# HighCurrentSwitches.net
KiCad netlist of a schematic drawn in Altium Designer
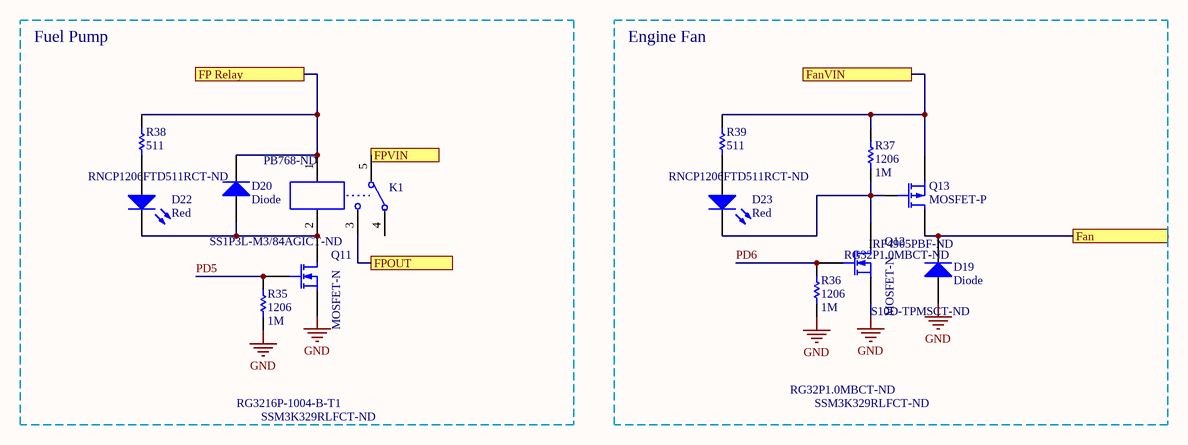
[diagram p0: HighCurrentSwitches.SchDoc]

(export (version "E")
  (design (tool "Eeschema 10.0.6"))
  (components
    (comp (ref "D19")
      (value "Diode")
      (footprint "SMC")
      (description "Default Diode")
      (fields
        (field (name "SUPPLIER PART NUMBER") "S10D-TPMSCT-ND")
        (field (name "PUBLISHER") "Altium Limited")
      )
      (libsource (lib "Miscellaneous Devices") (part "Diode"))
    )
    (comp (ref "D20")
      (value "Diode")
      (footprint "DO-220AA")
      (description "Switching diode")
      (fields
        (field (name "SUPPLIER PART NUMBER") "SS1P3L-M3/84AGICT-ND")
        (field (name "PUBLISHER") "Altium Limited")
      )
      (libsource (lib "Miscellaneous Devices") (part "Diode"))
    )
    (comp (ref "D22")
      (value "Red")
      (footprint "LEDC3216X120NRED")
      (description "Typical RED, GREEN, YELLOW, AMBER GaAs LED")
      (fields
        (field (name "MANUFACTURER") "Broadcom Avago")
        (field (name "MANUFACTURER PART NUMBER") "HSMY-C150")
        (field (name "PUBLISHER") "Altium Limited")
      )
      (libsource (lib "PowerDistLib") (part "LED2_2"))
    )
    (comp (ref "D23")
      (value "Red")
      (footprint "LEDC3216X120NRED")
      (description "Typical RED, GREEN, YELLOW, AMBER GaAs LED")
      (fields
        (field (name "MANUFACTURER") "Broadcom Avago")
        (field (name "MANUFACTURER PART NUMBER") "HSMY-C150")
        (field (name "PUBLISHER") "Altium Limited")
      )
      (libsource (lib "PowerDistLib") (part "LED2_2"))
    )
    (comp (ref "K1")
      (value "PB134012")
      (footprint "TECO-PB134-5_V")
      (fields (field (name "SUPPLIER PART NUMBER") "PB768-ND"))
      (libsource (lib "PowerDistLib") (part "PB134012"))
    )
    (comp (ref "Q11")
      (value "MOSFET-N")
      (footprint "SOT23-3")
      (description "N-Channel MOSFET")
      (fields
        (field (name "SUPPLIER PART NUMBER") "SSM3K329RLFCT-ND")
        (field (name "PUBLISHER") "Altium Limited")
      )
      (libsource (lib "Miscellaneous Devices") (part "MOSFET-N"))
    )
    (comp (ref "Q12")
      (value "MOSFET-N")
      (footprint "SOT23-3")
      (description "N-Channel MOSFET")
      (fields
        (field (name "SUPPLIER PART NUMBER") "SSM3K329RLFCT-ND")
        (field (name "PUBLISHER") "Altium Limited")
      )
      (libsource (lib "Miscellaneous Devices") (part "MOSFET-N"))
    )
    (comp (ref "Q13")
      (value "MOSFET-P")
      (footprint "TO-220AB")
      (description "P-Channel MOSFET")
      (fields
        (field (name "SUPPLIER PART NUMBER") "IRF4905PBF-ND")
        (field (name "PUBLISHER") "Altium Limited")
      )
      (libsource (lib "PowerDistLib") (part "MOSFET-P"))
    )
    (comp (ref "R35")
      (value "1206")
      (footprint "RESC3216X60N")
      (description "Resistor")
      (fields
        (field (name "ALTIUM_VALUE") "1M")
        (field (name "SUPPLIER PART NUMBER") "RG3216P-1004-B-T1")
        (field (name "PUBLISHER") "Altium Limited")
      )
      (libsource (lib "Miscellaneous Devices") (part "Res1"))
    )
    (comp (ref "R36")
      (value "1206")
      (footprint "RESC3216X60N")
      (description "Resistor")
      (fields
        (field (name "ALTIUM_VALUE") "1M")
        (field (name "SUPPLIER PART NUMBER") "RG32P1.0MBCT-ND")
        (field (name "PUBLISHER") "Altium Limited")
      )
      (libsource (lib "Miscellaneous Devices") (part "Res1"))
    )
    (comp (ref "R37")
      (value "1206")
      (footprint "RESC3216X60N")
      (description "Resistor")
      (fields
        (field (name "ALTIUM_VALUE") "1M")
        (field (name "SUPPLIER PART NUMBER") "RG32P1.0MBCT-ND")
        (field (name "PUBLISHER") "Altium Limited")
      )
      (libsource (lib "Miscellaneous Devices") (part "Res1"))
    )
    (comp (ref "R38")
      (value "511")
      (footprint "RESC3216X60N")
      (description "Resistor")
      (fields
        (field (name "SUPPLIER PART NUMBER") "RNCP1206FTD511RCT-ND")
        (field (name "PUBLISHER") "Altium Limited")
      )
      (libsource (lib "Miscellaneous Devices") (part "Res1"))
    )
    (comp (ref "R39")
      (value "511")
      (footprint "RESC3216X60N")
      (description "Resistor")
      (fields
        (field (name "SUPPLIER PART NUMBER") "RNCP1206FTD511RCT-ND")
        (field (name "PUBLISHER") "Altium Limited")
      )
      (libsource (lib "Miscellaneous Devices") (part "Res1"))
    )
  )
  (nets
    (net (code "1") (name "/FP Relay") (class "Default")
      (node (ref "D20") (pin "2") (pinfunction "K_2") (pintype "passive"))
      (node (ref "K1") (pin "1") (pinfunction "A1_1") (pintype "passive"))
      (node (ref "R38") (pin "1") (pinfunction "1_1") (pintype "passive"))
    )
    (net (code "2") (name "/FPOUT") (class "Default")
      (node (ref "K1") (pin "3") (pinfunction "14_3") (pintype "passive"))
    )
    (net (code "3") (name "/FPVIN") (class "Default")
      (node (ref "K1") (pin "5") (pinfunction "11_5") (pintype "passive"))
    )
    (net (code "4") (name "/Fan") (class "Default")
      (node (ref "D19") (pin "2") (pinfunction "K_2") (pintype "passive"))
      (node (ref "Q13") (pin "2") (pinfunction "D_2") (pintype "passive"))
    )
    (net (code "5") (name "/FanVIN") (class "Default")
      (node (ref "Q13") (pin "3") (pinfunction "S_3") (pintype "passive"))
      (node (ref "R37") (pin "2") (pinfunction "2_2") (pintype "passive"))
      (node (ref "R39") (pin "1") (pinfunction "1_1") (pintype "passive"))
    )
    (net (code "6") (name "/PD5") (class "Default")
      (node (ref "Q11") (pin "2") (pinfunction "G_2") (pintype "passive"))
      (node (ref "R35") (pin "2") (pinfunction "2_2") (pintype "passive"))
    )
    (net (code "7") (name "/PD6") (class "Default")
      (node (ref "Q12") (pin "2") (pinfunction "G_2") (pintype "passive"))
      (node (ref "R36") (pin "2") (pinfunction "2_2") (pintype "passive"))
    )
    (net (code "8") (name "GND") (class "Default")
      (node (ref "D19") (pin "1") (pinfunction "A_1") (pintype "passive"))
      (node (ref "Q11") (pin "3") (pinfunction "S_3") (pintype "passive"))
      (node (ref "Q12") (pin "3") (pinfunction "S_3") (pintype "passive"))
      (node (ref "R35") (pin "1") (pinfunction "1_1") (pintype "passive"))
      (node (ref "R36") (pin "1") (pinfunction "1_1") (pintype "passive"))
    )
    (net (code "9") (name "Net-(D20-A)") (class "Default")
      (node (ref "D20") (pin "1") (pinfunction "A_1") (pintype "passive"))
      (node (ref "D22") (pin "2") (pinfunction "K_2") (pintype "passive"))
      (node (ref "K1") (pin "2") (pinfunction "A2_2") (pintype "passive"))
      (node (ref "Q11") (pin "1") (pinfunction "D_1") (pintype "passive"))
    )
    (net (code "10") (name "Net-(D22-A)") (class "Default")
      (node (ref "D22") (pin "1") (pinfunction "A_1") (pintype "passive"))
      (node (ref "R38") (pin "2") (pinfunction "2_2") (pintype "passive"))
    )
    (net (code "11") (name "Net-(D23-A)") (class "Default")
      (node (ref "D23") (pin "1") (pinfunction "A_1") (pintype "passive"))
      (node (ref "R39") (pin "2") (pinfunction "2_2") (pintype "passive"))
    )
    (net (code "12") (name "Net-(D23-K)") (class "Default")
      (node (ref "D23") (pin "2") (pinfunction "K_2") (pintype "passive"))
      (node (ref "Q12") (pin "1") (pinfunction "D_1") (pintype "passive"))
      (node (ref "Q13") (pin "1") (pinfunction "G_1") (pintype "passive"))
      (node (ref "R37") (pin "1") (pinfunction "1_1") (pintype "passive"))
    )
    (net (code "13") (name "unconnected-(K1-12-Pad4)") (class "Default")
      (node (ref "K1") (pin "4") (pinfunction "12_4") (pintype "passive"))
    )
  )
)
